# isolated_NO_contacts.net
KiCad netlist of a schematic drawn in Altium Designer
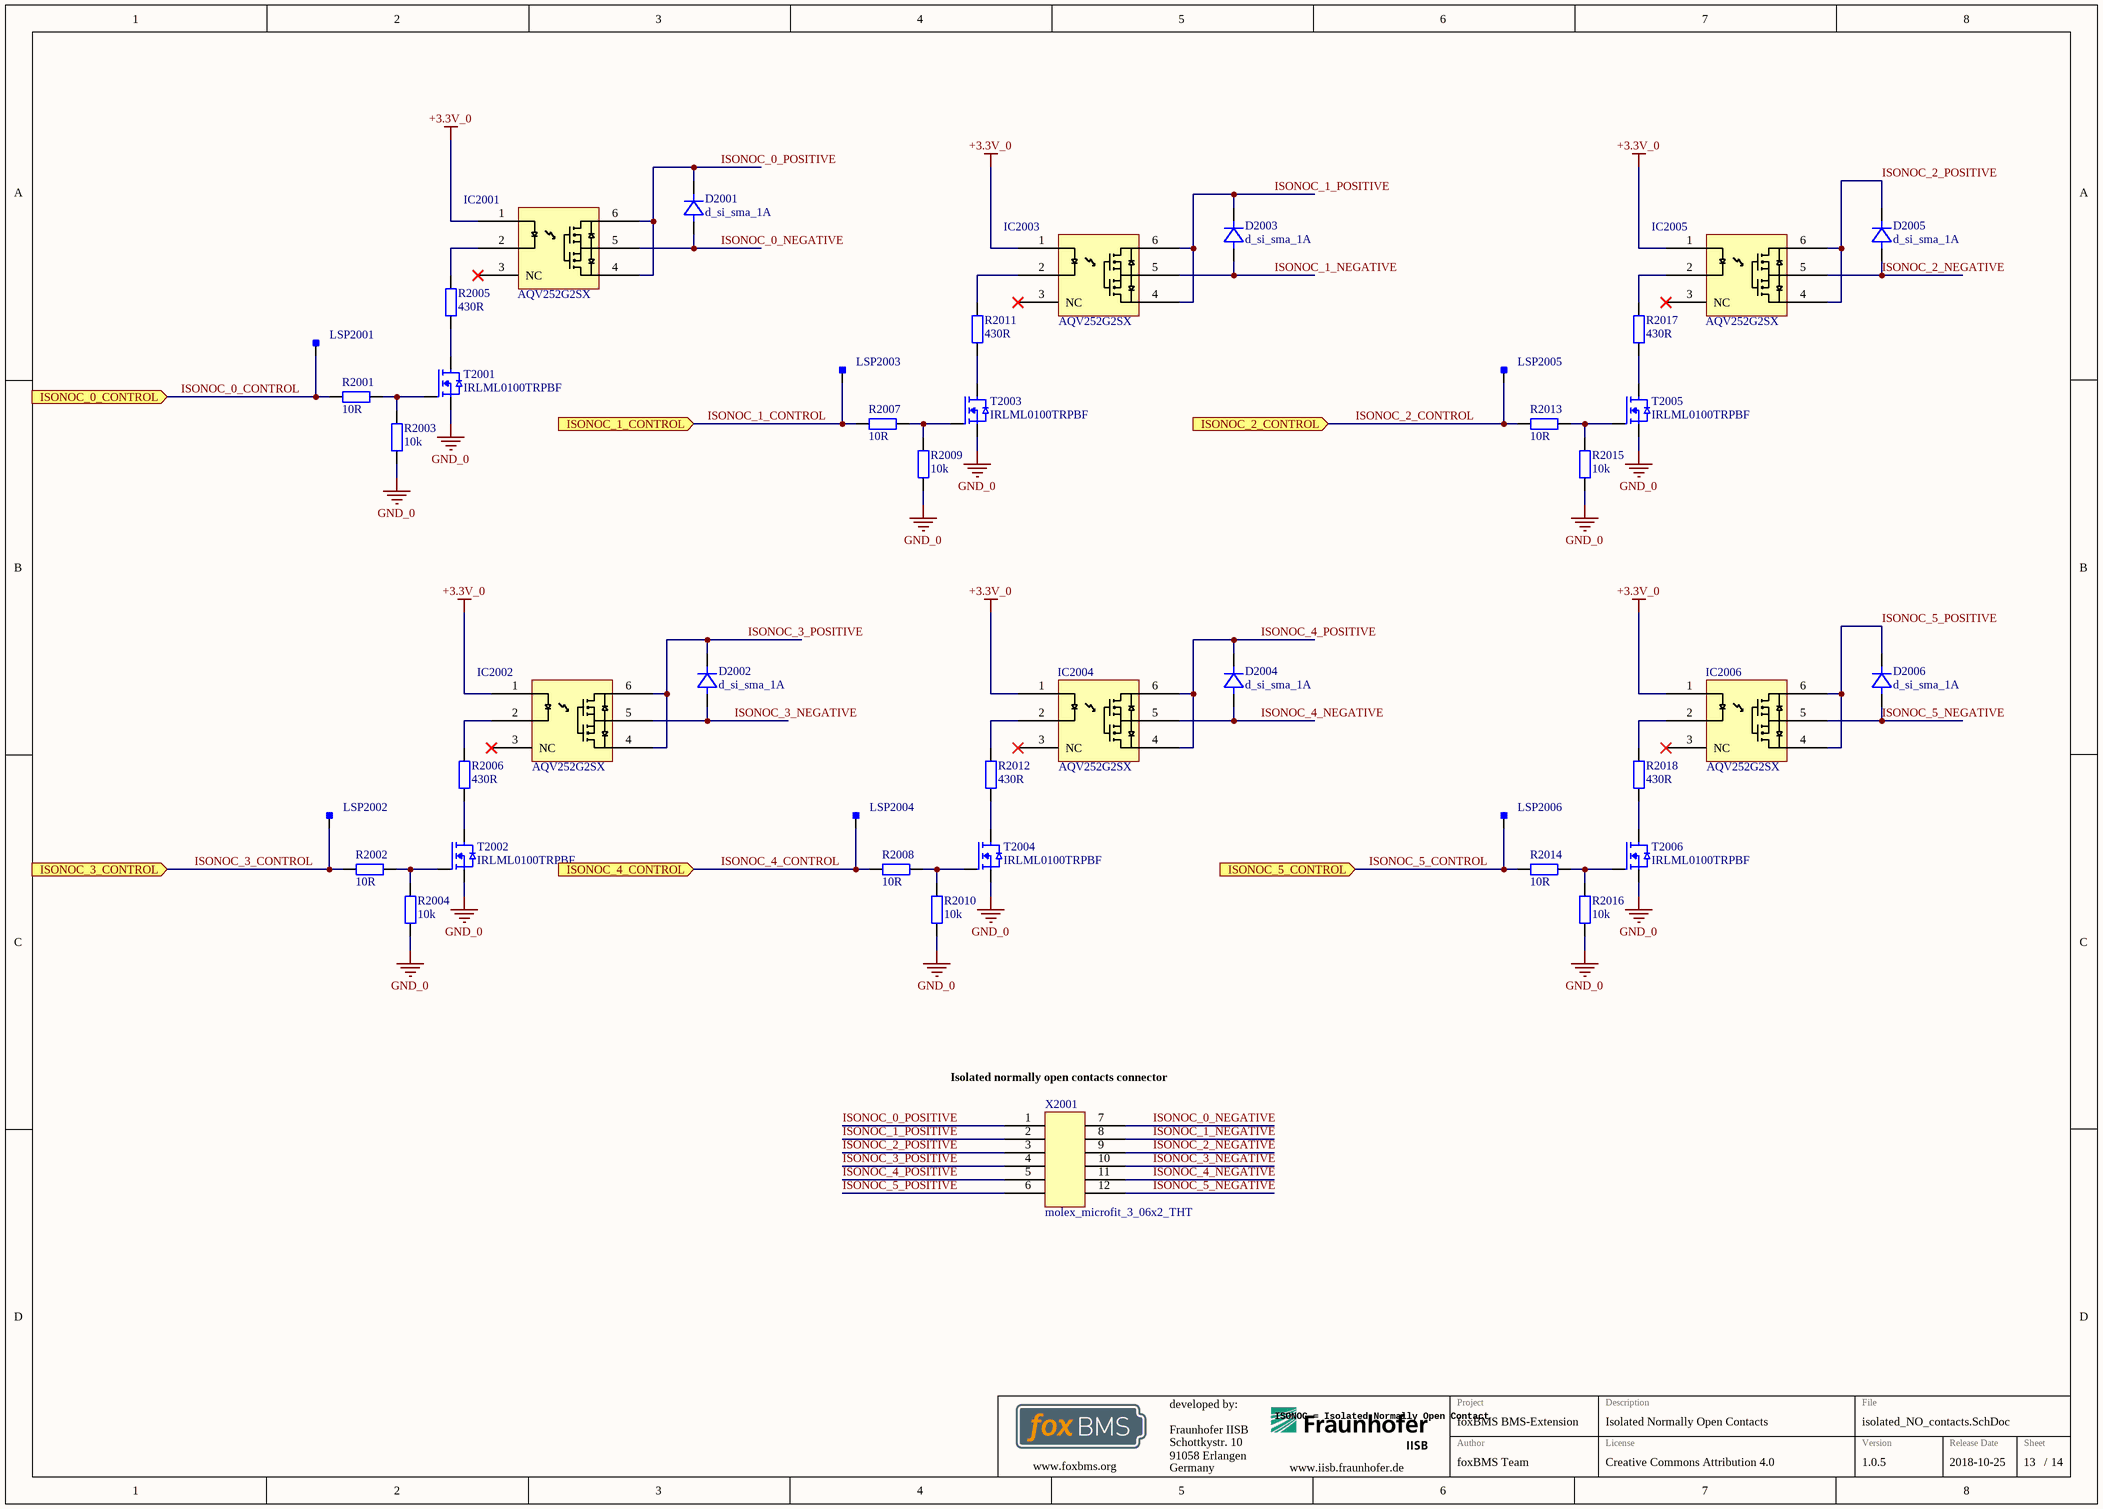
[diagram p0: isolated_NO_contacts.SchDoc]

(export (version "E")
  (design (tool "Eeschema 10.0.6"))
  (components
    (comp (ref "D2001")
      (value "d_si_sma_1A")
      (footprint "DIOM4326X24N")
      (description "Standard Recovery Diode, 100 V, 1 A, Single, 1 V, 2 µs, 30 A")
      (fields (field (name "MANUFACTURER") "ON Semiconductor"))
      (libsource (lib "OE750") (part "D"))
    )
    (comp (ref "D2002")
      (value "d_si_sma_1A")
      (footprint "DIOM4326X24N")
      (description "Standard Recovery Diode, 100 V, 1 A, Single, 1 V, 2 µs, 30 A")
      (fields (field (name "MANUFACTURER") "ON Semiconductor"))
      (libsource (lib "OE750") (part "D"))
    )
    (comp (ref "D2003")
      (value "d_si_sma_1A")
      (footprint "DIOM4326X24N")
      (description "Standard Recovery Diode, 100 V, 1 A, Single, 1 V, 2 µs, 30 A")
      (fields (field (name "MANUFACTURER") "ON Semiconductor"))
      (libsource (lib "OE750") (part "D"))
    )
    (comp (ref "D2004")
      (value "d_si_sma_1A")
      (footprint "DIOM4326X24N")
      (description "Standard Recovery Diode, 100 V, 1 A, Single, 1 V, 2 µs, 30 A")
      (fields (field (name "MANUFACTURER") "ON Semiconductor"))
      (libsource (lib "OE750") (part "D"))
    )
    (comp (ref "D2005")
      (value "d_si_sma_1A")
      (footprint "DIOM4326X24N")
      (description "Standard Recovery Diode, 100 V, 1 A, Single, 1 V, 2 µs, 30 A")
      (fields (field (name "MANUFACTURER") "ON Semiconductor"))
      (libsource (lib "OE750") (part "D"))
    )
    (comp (ref "D2006")
      (value "d_si_sma_1A")
      (footprint "DIOM4326X24N")
      (description "Standard Recovery Diode, 100 V, 1 A, Single, 1 V, 2 µs, 30 A")
      (fields (field (name "MANUFACTURER") "ON Semiconductor"))
      (libsource (lib "OE750") (part "D"))
    )
    (comp (ref "IC2001")
      (value "AQV252G2SX")
      (footprint "SOP254P680X220-6N")
      (description "PhotoMOS Relay")
      (fields (field (name "MANUFACTURER") "Panasonic"))
      (libsource (lib "OE750") (part "AQV252G2SX"))
    )
    (comp (ref "IC2002")
      (value "AQV252G2SX")
      (footprint "SOP254P680X220-6N")
      (description "PhotoMOS Relay")
      (fields (field (name "MANUFACTURER") "Panasonic"))
      (libsource (lib "OE750") (part "AQV252G2SX"))
    )
    (comp (ref "IC2003")
      (value "AQV252G2SX")
      (footprint "SOP254P680X220-6N")
      (description "PhotoMOS Relay")
      (fields (field (name "MANUFACTURER") "Panasonic"))
      (libsource (lib "OE750") (part "AQV252G2SX"))
    )
    (comp (ref "IC2004")
      (value "AQV252G2SX")
      (footprint "SOP254P680X220-6N")
      (description "PhotoMOS Relay")
      (fields (field (name "MANUFACTURER") "Panasonic"))
      (libsource (lib "OE750") (part "AQV252G2SX"))
    )
    (comp (ref "IC2005")
      (value "AQV252G2SX")
      (footprint "SOP254P680X220-6N")
      (description "PhotoMOS Relay")
      (fields (field (name "MANUFACTURER") "Panasonic"))
      (libsource (lib "OE750") (part "AQV252G2SX"))
    )
    (comp (ref "IC2006")
      (value "AQV252G2SX")
      (footprint "SOP254P680X220-6N")
      (description "PhotoMOS Relay")
      (fields (field (name "MANUFACTURER") "Panasonic"))
      (libsource (lib "OE750") (part "AQV252G2SX"))
    )
    (comp (ref "LSP2001")
      (value "Testpoint_Square")
      (footprint "Testpoint_S1")
      (description "Testpoint, square")
      (libsource (lib "OE750") (part "Testpoint_Square"))
    )
    (comp (ref "LSP2002")
      (value "Testpoint_Square")
      (footprint "Testpoint_S1")
      (description "Testpoint, square")
      (libsource (lib "OE750") (part "Testpoint_Square"))
    )
    (comp (ref "LSP2003")
      (value "Testpoint_Square")
      (footprint "Testpoint_S1")
      (description "Testpoint, square")
      (libsource (lib "OE750") (part "Testpoint_Square"))
    )
    (comp (ref "LSP2004")
      (value "Testpoint_Square")
      (footprint "Testpoint_S1")
      (description "Testpoint, square")
      (libsource (lib "OE750") (part "Testpoint_Square"))
    )
    (comp (ref "LSP2005")
      (value "Testpoint_Square")
      (footprint "Testpoint_S1")
      (description "Testpoint, square")
      (libsource (lib "OE750") (part "Testpoint_Square"))
    )
    (comp (ref "LSP2006")
      (value "Testpoint_Square")
      (footprint "Testpoint_S1")
      (description "Testpoint, square")
      (libsource (lib "OE750") (part "Testpoint_Square"))
    )
    (comp (ref "R2001")
      (value "10R")
      (footprint "RESC1608X05N")
      (description "SMD Resistor 10R 0603")
      (fields (field (name "PART NUMBER") "gen_R_10R_0603") (field (name "TOLERANCE") "1%"))
      (libsource (lib "OE750") (part "R"))
    )
    (comp (ref "R2002")
      (value "10R")
      (footprint "RESC1608X05N")
      (description "SMD Resistor 10R 0603")
      (fields (field (name "PART NUMBER") "gen_R_10R_0603") (field (name "TOLERANCE") "1%"))
      (libsource (lib "OE750") (part "R"))
    )
    (comp (ref "R2003")
      (value "10k")
      (footprint "RESC1608X05N")
      (description "SMD Resistor 10k 0603")
      (fields (field (name "PART NUMBER") "gen_R_10k_0603") (field (name "TOLERANCE") "1%"))
      (libsource (lib "OE750") (part "R"))
    )
    (comp (ref "R2004")
      (value "10k")
      (footprint "RESC1608X05N")
      (description "SMD Resistor 10k 0603")
      (fields (field (name "PART NUMBER") "gen_R_10k_0603") (field (name "TOLERANCE") "1%"))
      (libsource (lib "OE750") (part "R"))
    )
    (comp (ref "R2005")
      (value "430R")
      (footprint "RESC1608X05N")
      (description "SMD Resistor 430R 0603")
      (fields (field (name "PART NUMBER") "gen_R_430R_0603") (field (name "TOLERANCE") "1%"))
      (libsource (lib "OE750") (part "R"))
    )
    (comp (ref "R2006")
      (value "430R")
      (footprint "RESC1608X05N")
      (description "SMD Resistor 430R 0603")
      (fields (field (name "PART NUMBER") "gen_R_430R_0603") (field (name "TOLERANCE") "1%"))
      (libsource (lib "OE750") (part "R"))
    )
    (comp (ref "R2007")
      (value "10R")
      (footprint "RESC1608X05N")
      (description "SMD Resistor 10R 0603")
      (fields (field (name "PART NUMBER") "gen_R_10R_0603") (field (name "TOLERANCE") "1%"))
      (libsource (lib "OE750") (part "R"))
    )
    (comp (ref "R2008")
      (value "10R")
      (footprint "RESC1608X05N")
      (description "SMD Resistor 10R 0603")
      (fields (field (name "PART NUMBER") "gen_R_10R_0603") (field (name "TOLERANCE") "1%"))
      (libsource (lib "OE750") (part "R"))
    )
    (comp (ref "R2009")
      (value "10k")
      (footprint "RESC1608X05N")
      (description "SMD Resistor 10k 0603")
      (fields (field (name "PART NUMBER") "gen_R_10k_0603") (field (name "TOLERANCE") "1%"))
      (libsource (lib "OE750") (part "R"))
    )
    (comp (ref "R2010")
      (value "10k")
      (footprint "RESC1608X05N")
      (description "SMD Resistor 10k 0603")
      (fields (field (name "PART NUMBER") "gen_R_10k_0603") (field (name "TOLERANCE") "1%"))
      (libsource (lib "OE750") (part "R"))
    )
    (comp (ref "R2011")
      (value "430R")
      (footprint "RESC1608X05N")
      (description "SMD Resistor 430R 0603")
      (fields (field (name "PART NUMBER") "gen_R_430R_0603") (field (name "TOLERANCE") "1%"))
      (libsource (lib "OE750") (part "R"))
    )
    (comp (ref "R2012")
      (value "430R")
      (footprint "RESC1608X05N")
      (description "SMD Resistor 430R 0603")
      (fields (field (name "PART NUMBER") "gen_R_430R_0603") (field (name "TOLERANCE") "1%"))
      (libsource (lib "OE750") (part "R"))
    )
    (comp (ref "R2013")
      (value "10R")
      (footprint "RESC1608X05N")
      (description "SMD Resistor 10R 0603")
      (fields (field (name "PART NUMBER") "gen_R_10R_0603") (field (name "TOLERANCE") "1%"))
      (libsource (lib "OE750") (part "R"))
    )
    (comp (ref "R2014")
      (value "10R")
      (footprint "RESC1608X05N")
      (description "SMD Resistor 10R 0603")
      (fields (field (name "PART NUMBER") "gen_R_10R_0603") (field (name "TOLERANCE") "1%"))
      (libsource (lib "OE750") (part "R"))
    )
    (comp (ref "R2015")
      (value "10k")
      (footprint "RESC1608X05N")
      (description "SMD Resistor 10k 0603")
      (fields (field (name "PART NUMBER") "gen_R_10k_0603") (field (name "TOLERANCE") "1%"))
      (libsource (lib "OE750") (part "R"))
    )
    (comp (ref "R2016")
      (value "10k")
      (footprint "RESC1608X05N")
      (description "SMD Resistor 10k 0603")
      (fields (field (name "PART NUMBER") "gen_R_10k_0603") (field (name "TOLERANCE") "1%"))
      (libsource (lib "OE750") (part "R"))
    )
    (comp (ref "R2017")
      (value "430R")
      (footprint "RESC1608X05N")
      (description "SMD Resistor 430R 0603")
      (fields (field (name "PART NUMBER") "gen_R_430R_0603") (field (name "TOLERANCE") "1%"))
      (libsource (lib "OE750") (part "R"))
    )
    (comp (ref "R2018")
      (value "430R")
      (footprint "RESC1608X05N")
      (description "SMD Resistor 430R 0603")
      (fields (field (name "PART NUMBER") "gen_R_430R_0603") (field (name "TOLERANCE") "1%"))
      (libsource (lib "OE750") (part "R"))
    )
    (comp (ref "T2001")
      (value "IRLML0100TRPBF")
      (footprint "SOT95P237X110-3N")
      (description "MOSFET-Transistor, n-Kanal, 1.6 A, 100 V, 0.178 ohm, 10 V, 2.5 V")
      (fields (field (name "MANUFACTURER") "Infineon"))
      (libsource (lib "OE750") (part "NMOS"))
    )
    (comp (ref "T2002")
      (value "IRLML0100TRPBF")
      (footprint "SOT95P237X110-3N")
      (description "MOSFET-Transistor, n-Kanal, 1.6 A, 100 V, 0.178 ohm, 10 V, 2.5 V")
      (fields (field (name "MANUFACTURER") "Infineon"))
      (libsource (lib "OE750") (part "NMOS"))
    )
    (comp (ref "T2003")
      (value "IRLML0100TRPBF")
      (footprint "SOT95P237X110-3N")
      (description "MOSFET-Transistor, n-Kanal, 1.6 A, 100 V, 0.178 ohm, 10 V, 2.5 V")
      (fields (field (name "MANUFACTURER") "Infineon"))
      (libsource (lib "OE750") (part "NMOS"))
    )
    (comp (ref "T2004")
      (value "IRLML0100TRPBF")
      (footprint "SOT95P237X110-3N")
      (description "MOSFET-Transistor, n-Kanal, 1.6 A, 100 V, 0.178 ohm, 10 V, 2.5 V")
      (fields (field (name "MANUFACTURER") "Infineon"))
      (libsource (lib "OE750") (part "NMOS"))
    )
    (comp (ref "T2005")
      (value "IRLML0100TRPBF")
      (footprint "SOT95P237X110-3N")
      (description "MOSFET-Transistor, n-Kanal, 1.6 A, 100 V, 0.178 ohm, 10 V, 2.5 V")
      (fields (field (name "MANUFACTURER") "Infineon"))
      (libsource (lib "OE750") (part "NMOS"))
    )
    (comp (ref "T2006")
      (value "IRLML0100TRPBF")
      (footprint "SOT95P237X110-3N")
      (description "MOSFET-Transistor, n-Kanal, 1.6 A, 100 V, 0.178 ohm, 10 V, 2.5 V")
      (fields (field (name "MANUFACTURER") "Infineon"))
      (libsource (lib "OE750") (part "NMOS"))
    )
    (comp (ref "X2001")
      (value "molex_microfit_3_06x2_THT")
      (footprint "43045-1221")
      (fields (field (name "MANUFACTURER") "Molex"))
      (libsource (lib "OE750") (part "X6x2"))
    )
  )
  (nets
    (net (code "1") (name "+3.3V_0") (class "Default")
      (node (ref "IC2001") (pin "1") (pintype "passive"))
      (node (ref "IC2002") (pin "1") (pintype "passive"))
      (node (ref "IC2003") (pin "1") (pintype "passive"))
      (node (ref "IC2004") (pin "1") (pintype "passive"))
      (node (ref "IC2005") (pin "1") (pintype "passive"))
      (node (ref "IC2006") (pin "1") (pintype "passive"))
    )
    (net (code "2") (name "/ISONOC_0_CONTROL") (class "Default")
      (node (ref "LSP2001") (pin "1") (pinfunction "1_1") (pintype "passive"))
      (node (ref "R2001") (pin "2") (pinfunction "2_2") (pintype "passive"))
    )
    (net (code "3") (name "/ISONOC_0_NEGATIVE") (class "Default")
      (node (ref "D2001") (pin "2") (pinfunction "A_2") (pintype "passive"))
      (node (ref "IC2001") (pin "5") (pintype "passive"))
      (node (ref "X2001") (pin "7") (pintype "passive"))
    )
    (net (code "4") (name "/ISONOC_0_POSITIVE") (class "Default")
      (node (ref "D2001") (pin "1") (pinfunction "K_1") (pintype "passive"))
      (node (ref "IC2001") (pin "4") (pintype "passive"))
      (node (ref "IC2001") (pin "6") (pintype "passive"))
      (node (ref "X2001") (pin "1") (pintype "passive"))
    )
    (net (code "5") (name "/ISONOC_1_CONTROL") (class "Default")
      (node (ref "LSP2003") (pin "1") (pinfunction "1_1") (pintype "passive"))
      (node (ref "R2007") (pin "2") (pinfunction "2_2") (pintype "passive"))
    )
    (net (code "6") (name "/ISONOC_1_NEGATIVE") (class "Default")
      (node (ref "D2003") (pin "2") (pinfunction "A_2") (pintype "passive"))
      (node (ref "IC2003") (pin "5") (pintype "passive"))
      (node (ref "X2001") (pin "8") (pintype "passive"))
    )
    (net (code "7") (name "/ISONOC_1_POSITIVE") (class "Default")
      (node (ref "D2003") (pin "1") (pinfunction "K_1") (pintype "passive"))
      (node (ref "IC2003") (pin "4") (pintype "passive"))
      (node (ref "IC2003") (pin "6") (pintype "passive"))
      (node (ref "X2001") (pin "2") (pintype "passive"))
    )
    (net (code "8") (name "/ISONOC_2_CONTROL") (class "Default")
      (node (ref "LSP2005") (pin "1") (pinfunction "1_1") (pintype "passive"))
      (node (ref "R2013") (pin "2") (pinfunction "2_2") (pintype "passive"))
    )
    (net (code "9") (name "/ISONOC_2_NEGATIVE") (class "Default")
      (node (ref "D2005") (pin "2") (pinfunction "A_2") (pintype "passive"))
      (node (ref "IC2005") (pin "5") (pintype "passive"))
      (node (ref "X2001") (pin "9") (pintype "passive"))
    )
    (net (code "10") (name "/ISONOC_2_POSITIVE") (class "Default")
      (node (ref "D2005") (pin "1") (pinfunction "K_1") (pintype "passive"))
      (node (ref "IC2005") (pin "4") (pintype "passive"))
      (node (ref "IC2005") (pin "6") (pintype "passive"))
      (node (ref "X2001") (pin "3") (pintype "passive"))
    )
    (net (code "11") (name "/ISONOC_3_CONTROL") (class "Default")
      (node (ref "LSP2002") (pin "1") (pinfunction "1_1") (pintype "passive"))
      (node (ref "R2002") (pin "2") (pinfunction "2_2") (pintype "passive"))
    )
    (net (code "12") (name "/ISONOC_3_NEGATIVE") (class "Default")
      (node (ref "D2002") (pin "2") (pinfunction "A_2") (pintype "passive"))
      (node (ref "IC2002") (pin "5") (pintype "passive"))
      (node (ref "X2001") (pin "10") (pintype "passive"))
    )
    (net (code "13") (name "/ISONOC_3_POSITIVE") (class "Default")
      (node (ref "D2002") (pin "1") (pinfunction "K_1") (pintype "passive"))
      (node (ref "IC2002") (pin "4") (pintype "passive"))
      (node (ref "IC2002") (pin "6") (pintype "passive"))
      (node (ref "X2001") (pin "4") (pintype "passive"))
    )
    (net (code "14") (name "/ISONOC_4_CONTROL") (class "Default")
      (node (ref "LSP2004") (pin "1") (pinfunction "1_1") (pintype "passive"))
      (node (ref "R2008") (pin "2") (pinfunction "2_2") (pintype "passive"))
    )
    (net (code "15") (name "/ISONOC_4_NEGATIVE") (class "Default")
      (node (ref "D2004") (pin "2") (pinfunction "A_2") (pintype "passive"))
      (node (ref "IC2004") (pin "5") (pintype "passive"))
      (node (ref "X2001") (pin "11") (pintype "passive"))
    )
    (net (code "16") (name "/ISONOC_4_POSITIVE") (class "Default")
      (node (ref "D2004") (pin "1") (pinfunction "K_1") (pintype "passive"))
      (node (ref "IC2004") (pin "4") (pintype "passive"))
      (node (ref "IC2004") (pin "6") (pintype "passive"))
      (node (ref "X2001") (pin "5") (pintype "passive"))
    )
    (net (code "17") (name "/ISONOC_5_CONTROL") (class "Default")
      (node (ref "LSP2006") (pin "1") (pinfunction "1_1") (pintype "passive"))
      (node (ref "R2014") (pin "2") (pinfunction "2_2") (pintype "passive"))
    )
    (net (code "18") (name "/ISONOC_5_NEGATIVE") (class "Default")
      (node (ref "D2006") (pin "2") (pinfunction "A_2") (pintype "passive"))
      (node (ref "IC2006") (pin "5") (pintype "passive"))
      (node (ref "X2001") (pin "12") (pintype "passive"))
    )
    (net (code "19") (name "/ISONOC_5_POSITIVE") (class "Default")
      (node (ref "D2006") (pin "1") (pinfunction "K_1") (pintype "passive"))
      (node (ref "IC2006") (pin "4") (pintype "passive"))
      (node (ref "IC2006") (pin "6") (pintype "passive"))
      (node (ref "X2001") (pin "6") (pintype "passive"))
    )
    (net (code "20") (name "GND_0") (class "Default")
      (node (ref "R2003") (pin "1") (pinfunction "1_1") (pintype "passive"))
      (node (ref "R2004") (pin "1") (pinfunction "1_1") (pintype "passive"))
      (node (ref "R2009") (pin "1") (pinfunction "1_1") (pintype "passive"))
      (node (ref "R2010") (pin "1") (pinfunction "1_1") (pintype "passive"))
      (node (ref "R2015") (pin "1") (pinfunction "1_1") (pintype "passive"))
      (node (ref "R2016") (pin "1") (pinfunction "1_1") (pintype "passive"))
      (node (ref "T2001") (pin "S") (pinfunction "S_S") (pintype "passive"))
      (node (ref "T2002") (pin "S") (pinfunction "S_S") (pintype "passive"))
      (node (ref "T2003") (pin "S") (pinfunction "S_S") (pintype "passive"))
      (node (ref "T2004") (pin "S") (pinfunction "S_S") (pintype "passive"))
      (node (ref "T2005") (pin "S") (pinfunction "S_S") (pintype "passive"))
      (node (ref "T2006") (pin "S") (pinfunction "S_S") (pintype "passive"))
    )
    (net (code "21") (name "Net-(IC2001-Pad2)") (class "Default")
      (node (ref "IC2001") (pin "2") (pintype "power_in"))
      (node (ref "R2005") (pin "2") (pinfunction "2_2") (pintype "passive"))
    )
    (net (code "22") (name "Net-(IC2002-Pad2)") (class "Default")
      (node (ref "IC2002") (pin "2") (pintype "power_in"))
      (node (ref "R2006") (pin "2") (pinfunction "2_2") (pintype "passive"))
    )
    (net (code "23") (name "Net-(IC2003-Pad2)") (class "Default")
      (node (ref "IC2003") (pin "2") (pintype "power_in"))
      (node (ref "R2011") (pin "2") (pinfunction "2_2") (pintype "passive"))
    )
    (net (code "24") (name "Net-(IC2004-Pad2)") (class "Default")
      (node (ref "IC2004") (pin "2") (pintype "power_in"))
      (node (ref "R2012") (pin "2") (pinfunction "2_2") (pintype "passive"))
    )
    (net (code "25") (name "Net-(IC2005-Pad2)") (class "Default")
      (node (ref "IC2005") (pin "2") (pintype "power_in"))
      (node (ref "R2017") (pin "2") (pinfunction "2_2") (pintype "passive"))
    )
    (net (code "26") (name "Net-(IC2006-Pad2)") (class "Default")
      (node (ref "IC2006") (pin "2") (pintype "power_in"))
      (node (ref "R2018") (pin "2") (pinfunction "2_2") (pintype "passive"))
    )
    (net (code "27") (name "Net-(R2001-Pad1)") (class "Default")
      (node (ref "R2001") (pin "1") (pinfunction "1_1") (pintype "passive"))
      (node (ref "R2003") (pin "2") (pinfunction "2_2") (pintype "passive"))
      (node (ref "T2001") (pin "G") (pinfunction "G_G") (pintype "passive"))
    )
    (net (code "28") (name "Net-(R2002-Pad1)") (class "Default")
      (node (ref "R2002") (pin "1") (pinfunction "1_1") (pintype "passive"))
      (node (ref "R2004") (pin "2") (pinfunction "2_2") (pintype "passive"))
      (node (ref "T2002") (pin "G") (pinfunction "G_G") (pintype "passive"))
    )
    (net (code "29") (name "Net-(R2005-Pad1)") (class "Default")
      (node (ref "R2005") (pin "1") (pinfunction "1_1") (pintype "passive"))
      (node (ref "T2001") (pin "D") (pinfunction "D_D") (pintype "passive"))
    )
    (net (code "30") (name "Net-(R2006-Pad1)") (class "Default")
      (node (ref "R2006") (pin "1") (pinfunction "1_1") (pintype "passive"))
      (node (ref "T2002") (pin "D") (pinfunction "D_D") (pintype "passive"))
    )
    (net (code "31") (name "Net-(R2007-Pad1)") (class "Default")
      (node (ref "R2007") (pin "1") (pinfunction "1_1") (pintype "passive"))
      (node (ref "R2009") (pin "2") (pinfunction "2_2") (pintype "passive"))
      (node (ref "T2003") (pin "G") (pinfunction "G_G") (pintype "passive"))
    )
    (net (code "32") (name "Net-(R2008-Pad1)") (class "Default")
      (node (ref "R2008") (pin "1") (pinfunction "1_1") (pintype "passive"))
      (node (ref "R2010") (pin "2") (pinfunction "2_2") (pintype "passive"))
      (node (ref "T2004") (pin "G") (pinfunction "G_G") (pintype "passive"))
    )
    (net (code "33") (name "Net-(R2011-Pad1)") (class "Default")
      (node (ref "R2011") (pin "1") (pinfunction "1_1") (pintype "passive"))
      (node (ref "T2003") (pin "D") (pinfunction "D_D") (pintype "passive"))
    )
    (net (code "34") (name "Net-(R2012-Pad1)") (class "Default")
      (node (ref "R2012") (pin "1") (pinfunction "1_1") (pintype "passive"))
      (node (ref "T2004") (pin "D") (pinfunction "D_D") (pintype "passive"))
    )
    (net (code "35") (name "Net-(R2013-Pad1)") (class "Default")
      (node (ref "R2013") (pin "1") (pinfunction "1_1") (pintype "passive"))
      (node (ref "R2015") (pin "2") (pinfunction "2_2") (pintype "passive"))
      (node (ref "T2005") (pin "G") (pinfunction "G_G") (pintype "passive"))
    )
    (net (code "36") (name "Net-(R2014-Pad1)") (class "Default")
      (node (ref "R2014") (pin "1") (pinfunction "1_1") (pintype "passive"))
      (node (ref "R2016") (pin "2") (pinfunction "2_2") (pintype "passive"))
      (node (ref "T2006") (pin "G") (pinfunction "G_G") (pintype "passive"))
    )
    (net (code "37") (name "Net-(R2017-Pad1)") (class "Default")
      (node (ref "R2017") (pin "1") (pinfunction "1_1") (pintype "passive"))
      (node (ref "T2005") (pin "D") (pinfunction "D_D") (pintype "passive"))
    )
    (net (code "38") (name "Net-(R2018-Pad1)") (class "Default")
      (node (ref "R2018") (pin "1") (pinfunction "1_1") (pintype "passive"))
      (node (ref "T2006") (pin "D") (pinfunction "D_D") (pintype "passive"))
    )
    (net (code "39") (name "unconnected-(IC2001-NC-Pad3)") (class "Default")
      (node (ref "IC2001") (pin "3") (pinfunction "NC_3") (pintype "passive+no_connect"))
    )
    (net (code "40") (name "unconnected-(IC2002-NC-Pad3)") (class "Default")
      (node (ref "IC2002") (pin "3") (pinfunction "NC_3") (pintype "passive+no_connect"))
    )
    (net (code "41") (name "unconnected-(IC2003-NC-Pad3)") (class "Default")
      (node (ref "IC2003") (pin "3") (pinfunction "NC_3") (pintype "passive+no_connect"))
    )
    (net (code "42") (name "unconnected-(IC2004-NC-Pad3)") (class "Default")
      (node (ref "IC2004") (pin "3") (pinfunction "NC_3") (pintype "passive+no_connect"))
    )
    (net (code "43") (name "unconnected-(IC2005-NC-Pad3)") (class "Default")
      (node (ref "IC2005") (pin "3") (pinfunction "NC_3") (pintype "passive+no_connect"))
    )
    (net (code "44") (name "unconnected-(IC2006-NC-Pad3)") (class "Default")
      (node (ref "IC2006") (pin "3") (pinfunction "NC_3") (pintype "passive+no_connect"))
    )
  )
)
